# JBCproject.net
KiCad netlist of a schematic drawn in EAGLE
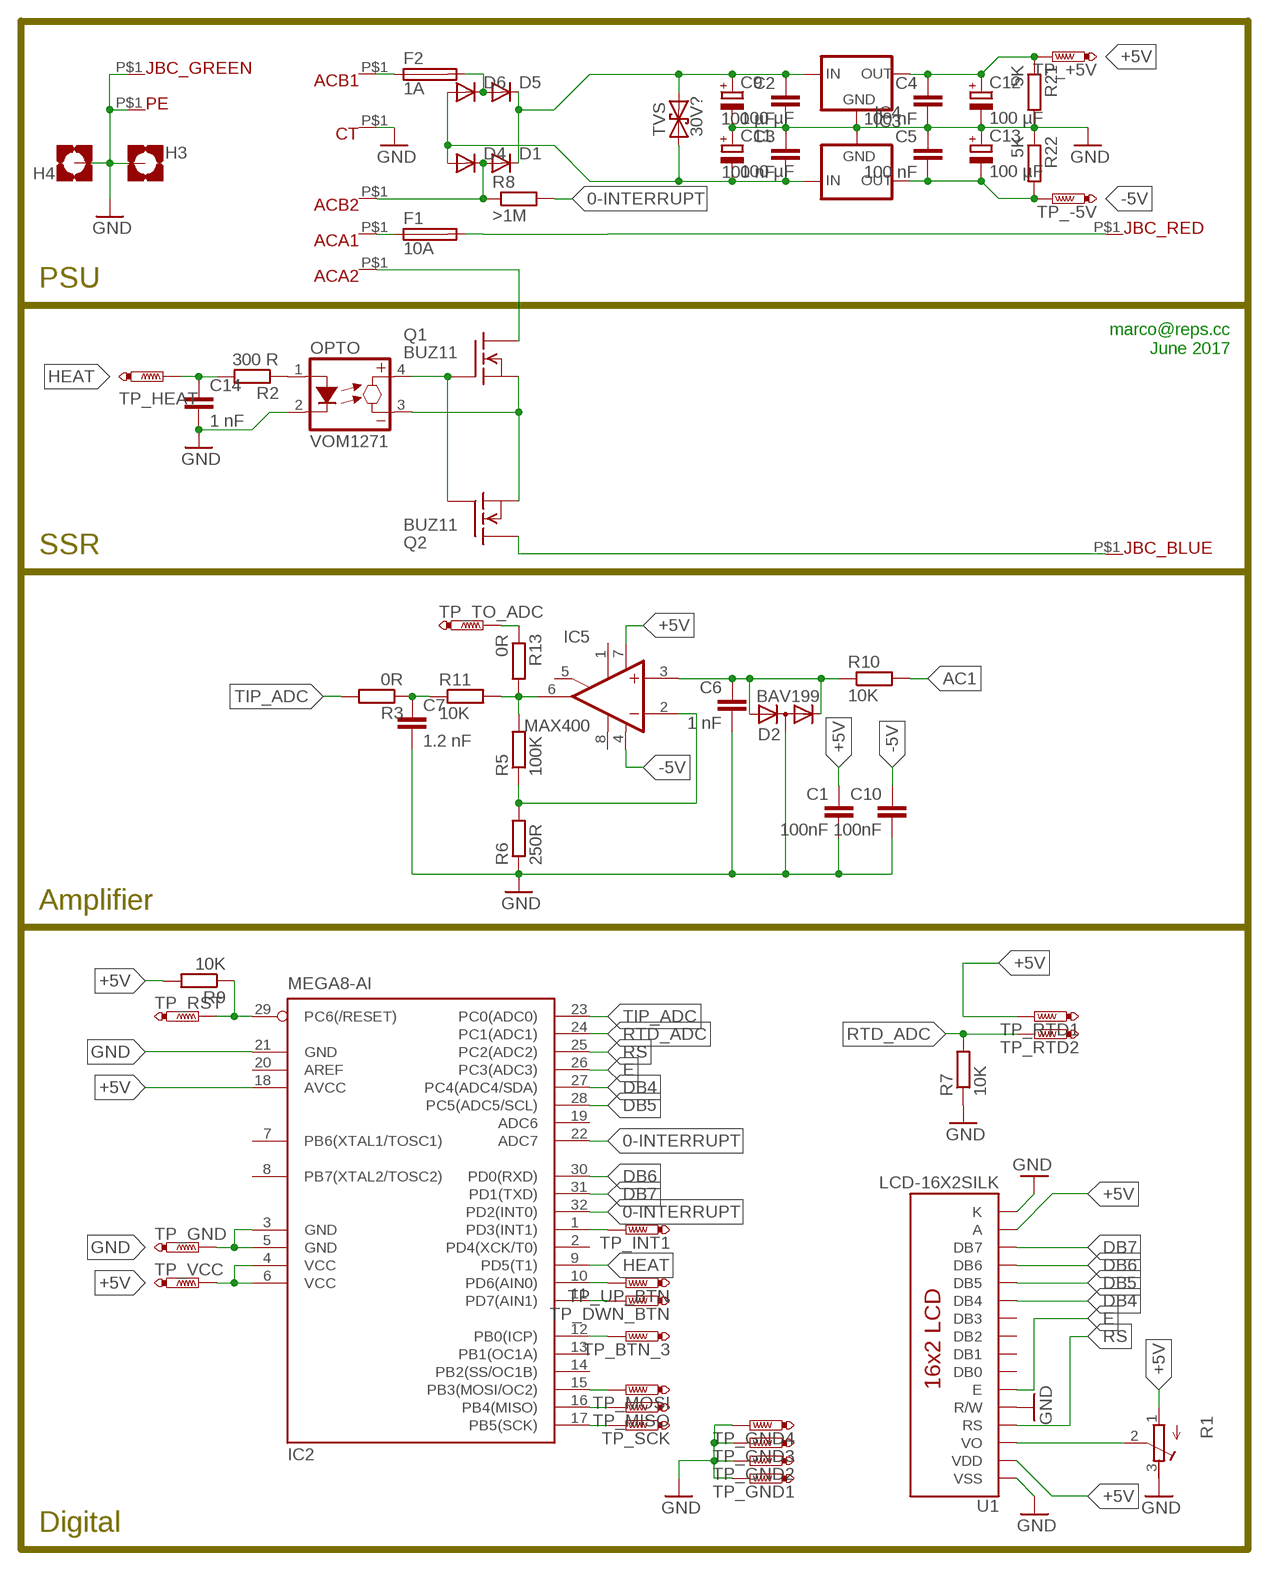
[diagram p0: schematic, sheet 1]

(export (version "E")
  (design (tool "Eeschema 10.0.6"))
  (components
    (comp (ref "ACA1")
      (value "1MMPIN")
      (footprint "eagle-import:1MMPIN")
      (libsource (lib "eagle-import") (part "1MMPIN"))
    )
    (comp (ref "ACA2")
      (value "1MMPIN")
      (footprint "eagle-import:1MMPIN")
      (libsource (lib "eagle-import") (part "1MMPIN"))
    )
    (comp (ref "ACB1")
      (value "1MMPIN")
      (footprint "eagle-import:1MMPIN")
      (libsource (lib "eagle-import") (part "1MMPIN"))
    )
    (comp (ref "ACB2")
      (value "1MMPIN")
      (footprint "eagle-import:1MMPIN")
      (libsource (lib "eagle-import") (part "1MMPIN"))
    )
    (comp (ref "C1")
      (value "100nF")
      (footprint "eagle-import:C1206")
      (libsource (lib "eagle-import") (part "C-EUC1206"))
    )
    (comp (ref "C2")
      (value "100 µF")
      (footprint "eagle-import:C1206")
      (libsource (lib "eagle-import") (part "C-EUC1206"))
    )
    (comp (ref "C3")
      (value "100 nF")
      (footprint "eagle-import:C1206")
      (libsource (lib "eagle-import") (part "C-EUC1206"))
    )
    (comp (ref "C4")
      (value "100 nF")
      (footprint "eagle-import:C1206")
      (libsource (lib "eagle-import") (part "C-EUC1206"))
    )
    (comp (ref "C5")
      (value "100 nF")
      (footprint "eagle-import:C1206")
      (libsource (lib "eagle-import") (part "C-EUC1206"))
    )
    (comp (ref "C6")
      (value "1 nF")
      (footprint "eagle-import:C1206")
      (libsource (lib "eagle-import") (part "C-EUC1206"))
    )
    (comp (ref "C7")
      (value "1.2 nF")
      (footprint "eagle-import:C1206")
      (libsource (lib "eagle-import") (part "C-EUC1206"))
    )
    (comp (ref "C9")
      (value "100 µF")
      (footprint "eagle-import:175TMP-0810")
      (libsource (lib "eagle-import") (part "CPOL-EU175TMP-0810"))
    )
    (comp (ref "C10")
      (value "100nF")
      (footprint "eagle-import:C1206")
      (libsource (lib "eagle-import") (part "C-EUC1206"))
    )
    (comp (ref "C11")
      (value "100 µF")
      (footprint "eagle-import:175TMP-0810")
      (libsource (lib "eagle-import") (part "CPOL-EU175TMP-0810"))
    )
    (comp (ref "C12")
      (value "100 µF")
      (footprint "eagle-import:175TMP-0810")
      (libsource (lib "eagle-import") (part "CPOL-EU175TMP-0810"))
    )
    (comp (ref "C13")
      (value "100 µF")
      (footprint "eagle-import:175TMP-0810")
      (libsource (lib "eagle-import") (part "CPOL-EU175TMP-0810"))
    )
    (comp (ref "C14")
      (value "1 nF")
      (footprint "eagle-import:C1206")
      (libsource (lib "eagle-import") (part "C-EUC1206"))
    )
    (comp (ref "CT")
      (value "1MMPIN")
      (footprint "eagle-import:1MMPIN")
      (libsource (lib "eagle-import") (part "1MMPIN"))
    )
    (comp (ref "D1")
      (value "ES2D")
      (footprint "eagle-import:SMB")
      (libsource (lib "eagle-import") (part "ES2D"))
    )
    (comp (ref "D2")
      (value "BAV199")
      (footprint "eagle-import:SOT23")
      (libsource (lib "eagle-import") (part "BAV199"))
    )
    (comp (ref "D4")
      (value "ES2D")
      (footprint "eagle-import:SMB")
      (libsource (lib "eagle-import") (part "ES2D"))
    )
    (comp (ref "D5")
      (value "ES2D")
      (footprint "eagle-import:SMB")
      (libsource (lib "eagle-import") (part "ES2D"))
    )
    (comp (ref "D6")
      (value "ES2D")
      (footprint "eagle-import:SMB")
      (libsource (lib "eagle-import") (part "ES2D"))
    )
    (comp (ref "F1")
      (value "10A")
      (footprint "eagle-import:PICOFUSE")
      (libsource (lib "eagle-import") (part "PICOFUSE"))
    )
    (comp (ref "F2")
      (value "1A")
      (footprint "eagle-import:PICOFUSE")
      (libsource (lib "eagle-import") (part "PICOFUSE"))
    )
    (comp (ref "H3")
      (value "MOUNT-PAD-SQUARE3.0")
      (footprint "eagle-import:3,0-PAD-SQUARE")
      (libsource (lib "eagle-import") (part "MOUNT-PAD-SQUARE3.0"))
    )
    (comp (ref "H4")
      (value "MOUNT-PAD-SQUARE3.0")
      (footprint "eagle-import:3,0-PAD-SQUARE")
      (libsource (lib "eagle-import") (part "MOUNT-PAD-SQUARE3.0"))
    )
    (comp (ref "IC2")
      (value "MEGA8-AI")
      (footprint "eagle-import:TQFP32-08")
      (fields (field (name "MPN") "ATMEGA8-16AU"))
      (libsource (lib "eagle-import") (part "MEGA8-AI"))
    )
    (comp (ref "IC3")
      (value "78XXS")
      (footprint "eagle-import:78XXS")
      (libsource (lib "eagle-import") (part "78XXS"))
    )
    (comp (ref "IC4")
      (value "79XXS")
      (footprint "eagle-import:79XXS")
      (libsource (lib "eagle-import") (part "79XXS"))
    )
    (comp (ref "IC5")
      (value "MAX400")
      (footprint "eagle-import:DIL08")
      (libsource (lib "eagle-import") (part "MAX400MJA"))
    )
    (comp (ref "JBC_BLUE")
      (value "1MMPIN")
      (footprint "eagle-import:1MMPIN")
      (libsource (lib "eagle-import") (part "1MMPIN"))
    )
    (comp (ref "JBC_GREEN")
      (value "1MMPIN")
      (footprint "eagle-import:1MMPIN")
      (libsource (lib "eagle-import") (part "1MMPIN"))
    )
    (comp (ref "JBC_RED")
      (value "1MMPIN")
      (footprint "eagle-import:1MMPIN")
      (libsource (lib "eagle-import") (part "1MMPIN"))
    )
    (comp (ref "OPTO")
      (value "VOM1271")
      (footprint "eagle-import:SOP-4")
      (libsource (lib "eagle-import") (part "VOM1271"))
    )
    (comp (ref "PE")
      (value "1MMPIN")
      (footprint "eagle-import:1MMPIN")
      (libsource (lib "eagle-import") (part "1MMPIN"))
    )
    (comp (ref "Q1")
      (value "BUZ11")
      (footprint "eagle-import:TO220")
      (libsource (lib "eagle-import") (part "BUZ11"))
    )
    (comp (ref "Q2")
      (value "BUZ11")
      (footprint "eagle-import:TO220")
      (libsource (lib "eagle-import") (part "BUZ11"))
    )
    (comp (ref "R1")
      (value "R-TRIMM4G/J")
      (footprint "eagle-import:RTRIM4G_J")
      (libsource (lib "eagle-import") (part "R-TRIMM4G/J"))
    )
    (comp (ref "R2")
      (value "300 R")
      (footprint "eagle-import:R1206")
      (libsource (lib "eagle-import") (part "R-EU_R1206"))
    )
    (comp (ref "R3")
      (value "0R")
      (footprint "eagle-import:R1206")
      (libsource (lib "eagle-import") (part "R-EU_R1206"))
    )
    (comp (ref "R5")
      (value "100K")
      (footprint "eagle-import:R1206")
      (libsource (lib "eagle-import") (part "R-EU_R1206"))
    )
    (comp (ref "R6")
      (value "250R")
      (footprint "eagle-import:R1206")
      (libsource (lib "eagle-import") (part "R-EU_R1206"))
    )
    (comp (ref "R7")
      (value "10K")
      (footprint "eagle-import:R1206")
      (libsource (lib "eagle-import") (part "R-EU_R1206"))
    )
    (comp (ref "R8")
      (value ">1M")
      (footprint "eagle-import:R1206")
      (libsource (lib "eagle-import") (part "R-EU_R1206"))
    )
    (comp (ref "R9")
      (value "10K")
      (footprint "eagle-import:R1206")
      (libsource (lib "eagle-import") (part "R-EU_R1206"))
    )
    (comp (ref "R10")
      (value "10K")
      (footprint "eagle-import:R1206")
      (libsource (lib "eagle-import") (part "R-EU_R1206"))
    )
    (comp (ref "R11")
      (value "10K")
      (footprint "eagle-import:R1206")
      (libsource (lib "eagle-import") (part "R-EU_R1206"))
    )
    (comp (ref "R13")
      (value "0R")
      (footprint "eagle-import:R1206")
      (libsource (lib "eagle-import") (part "R-EU_R1206"))
    )
    (comp (ref "R21")
      (value "5K")
      (footprint "eagle-import:R1206")
      (libsource (lib "eagle-import") (part "R-EU_R1206"))
    )
    (comp (ref "R22")
      (value "5K")
      (footprint "eagle-import:R1206")
      (libsource (lib "eagle-import") (part "R-EU_R1206"))
    )
    (comp (ref "TP_+5V")
      (value "PTR1TP20R")
      (footprint "eagle-import:TP20R")
      (libsource (lib "eagle-import") (part "PTR1TP20R"))
    )
    (comp (ref "TP_-5V")
      (value "PTR1TP20R")
      (footprint "eagle-import:TP20R")
      (libsource (lib "eagle-import") (part "PTR1TP20R"))
    )
    (comp (ref "TP_BTN_3")
      (value "PTR1TP20R")
      (footprint "eagle-import:TP20R")
      (libsource (lib "eagle-import") (part "PTR1TP20R"))
    )
    (comp (ref "TP_DWN_BTN")
      (value "PTR1TP20R")
      (footprint "eagle-import:TP20R")
      (libsource (lib "eagle-import") (part "PTR1TP20R"))
    )
    (comp (ref "TP_GND")
      (value "PTR1TP20R")
      (footprint "eagle-import:TP20R")
      (libsource (lib "eagle-import") (part "PTR1TP20R"))
    )
    (comp (ref "TP_GND1")
      (value "PTR1TP20R")
      (footprint "eagle-import:TP20R")
      (libsource (lib "eagle-import") (part "PTR1TP20R"))
    )
    (comp (ref "TP_GND2")
      (value "PTR1TP20R")
      (footprint "eagle-import:TP20R")
      (libsource (lib "eagle-import") (part "PTR1TP20R"))
    )
    (comp (ref "TP_GND3")
      (value "PTR1TP20R")
      (footprint "eagle-import:TP20R")
      (libsource (lib "eagle-import") (part "PTR1TP20R"))
    )
    (comp (ref "TP_GND4")
      (value "PTR1TP20R")
      (footprint "eagle-import:TP20R")
      (libsource (lib "eagle-import") (part "PTR1TP20R"))
    )
    (comp (ref "TP_HEAT")
      (value "PTR1TP20R")
      (footprint "eagle-import:TP20R")
      (libsource (lib "eagle-import") (part "PTR1TP20R"))
    )
    (comp (ref "TP_INT1")
      (value "PTR1TP20R")
      (footprint "eagle-import:TP20R")
      (libsource (lib "eagle-import") (part "PTR1TP20R"))
    )
    (comp (ref "TP_MISO")
      (value "PTR1TP20R")
      (footprint "eagle-import:TP20R")
      (libsource (lib "eagle-import") (part "PTR1TP20R"))
    )
    (comp (ref "TP_MOSI")
      (value "PTR1TP20R")
      (footprint "eagle-import:TP20R")
      (libsource (lib "eagle-import") (part "PTR1TP20R"))
    )
    (comp (ref "TP_RST")
      (value "PTR1TP20R")
      (footprint "eagle-import:TP20R")
      (libsource (lib "eagle-import") (part "PTR1TP20R"))
    )
    (comp (ref "TP_RTD1")
      (value "PTR1TP20R")
      (footprint "eagle-import:TP20R")
      (libsource (lib "eagle-import") (part "PTR1TP20R"))
    )
    (comp (ref "TP_RTD2")
      (value "PTR1TP20R")
      (footprint "eagle-import:TP20R")
      (libsource (lib "eagle-import") (part "PTR1TP20R"))
    )
    (comp (ref "TP_SCK")
      (value "PTR1TP20R")
      (footprint "eagle-import:TP20R")
      (libsource (lib "eagle-import") (part "PTR1TP20R"))
    )
    (comp (ref "TP_TO_ADC")
      (value "PTR1TP20R")
      (footprint "eagle-import:TP20R")
      (libsource (lib "eagle-import") (part "PTR1TP20R"))
    )
    (comp (ref "TP_UP_BTN")
      (value "PTR1TP20R")
      (footprint "eagle-import:TP20R")
      (libsource (lib "eagle-import") (part "PTR1TP20R"))
    )
    (comp (ref "TP_VCC")
      (value "PTR1TP20R")
      (footprint "eagle-import:TP20R")
      (libsource (lib "eagle-import") (part "PTR1TP20R"))
    )
    (comp (ref "TVS")
      (value "30V?")
      (footprint "eagle-import:SMA-DIODE")
      (libsource (lib "eagle-import") (part "TVS"))
    )
    (comp (ref "U1")
      (value "LCD-16X2SILK")
      (footprint "eagle-import:LCD-16X2")
      (libsource (lib "eagle-import") (part "LCD-16X2SILK"))
    )
  )
  (nets
    (net (code "1") (name "+5V") (class "Default")
      (node (ref "C1") (pin "1") (pinfunction "1_1") (pintype "passive"))
      (node (ref "C12") (pin "+") (pinfunction "+_+") (pintype "passive"))
      (node (ref "C4") (pin "1") (pinfunction "1_1") (pintype "passive"))
      (node (ref "IC2") (pin "18") (pinfunction "AVCC_18") (pintype "power_in"))
      (node (ref "IC2") (pin "4") (pinfunction "VCC_4") (pintype "power_in"))
      (node (ref "IC2") (pin "6") (pinfunction "VCC_6") (pintype "power_in"))
      (node (ref "IC3") (pin "OUT") (pinfunction "OUT_OUT") (pintype "passive"))
      (node (ref "IC5") (pin "7") (pinfunction "V+_7") (pintype "power_in"))
      (node (ref "R1") (pin "1") (pinfunction "A_1") (pintype "passive"))
      (node (ref "R21") (pin "1") (pinfunction "1_1") (pintype "passive"))
      (node (ref "R9") (pin "2") (pinfunction "2_2") (pintype "passive"))
      (node (ref "TP_+5V") (pin "TP") (pinfunction "TP_TP") (pintype "input"))
      (node (ref "TP_RTD1") (pin "TP") (pinfunction "TP_TP") (pintype "input"))
      (node (ref "TP_VCC") (pin "TP") (pinfunction "TP_TP") (pintype "input"))
      (node (ref "U1") (pin "15") (pinfunction "A_15") (pintype "power_in"))
      (node (ref "U1") (pin "2") (pinfunction "VDD_2") (pintype "power_in"))
    )
    (net (code "2") (name "-5V") (class "Default")
      (node (ref "C10") (pin "1") (pinfunction "1_1") (pintype "passive"))
      (node (ref "C13") (pin "-") (pinfunction "-_-") (pintype "passive"))
      (node (ref "C5") (pin "2") (pinfunction "2_2") (pintype "passive"))
      (node (ref "IC4") (pin "OUT") (pinfunction "OUT_OUT") (pintype "passive"))
      (node (ref "IC5") (pin "4") (pinfunction "V-_4") (pintype "power_in"))
      (node (ref "R22") (pin "2") (pinfunction "2_2") (pintype "passive"))
      (node (ref "TP_-5V") (pin "TP") (pinfunction "TP_TP") (pintype "input"))
    )
    (net (code "3") (name "/OPAMPOUT") (class "Default")
      (node (ref "IC5") (pin "6") (pinfunction "OUT_6") (pintype "output"))
      (node (ref "R11") (pin "2") (pinfunction "2_2") (pintype "passive"))
      (node (ref "R13") (pin "1") (pinfunction "1_1") (pintype "passive"))
      (node (ref "R13") (pin "2") (pinfunction "2_2") (pintype "passive"))
      (node (ref "R5") (pin "2") (pinfunction "2_2") (pintype "passive"))
      (node (ref "TP_TO_ADC") (pin "TP") (pinfunction "TP_TP") (pintype "input"))
    )
    (net (code "4") (name "0-INTERRUPT") (class "Default")
      (node (ref "IC2") (pin "22") (pinfunction "ADC7_22") (pintype "bidirectional"))
      (node (ref "IC2") (pin "32") (pinfunction "PD2(INT0)_32") (pintype "bidirectional"))
      (node (ref "R8") (pin "2") (pinfunction "2_2") (pintype "passive"))
    )
    (net (code "5") (name "AC1") (class "Default")
      (node (ref "F1") (pin "2") (pinfunction "2_2") (pintype "passive"))
      (node (ref "JBC_RED") (pin "P$1") (pinfunction "P$1_P$1") (pintype "bidirectional"))
      (node (ref "R10") (pin "2") (pinfunction "2_2") (pintype "passive"))
    )
    (net (code "6") (name "DB4") (class "Default")
      (node (ref "IC2") (pin "27") (pinfunction "PC4(ADC4/SDA)_27") (pintype "bidirectional"))
      (node (ref "U1") (pin "11") (pinfunction "DB4_11") (pintype "bidirectional"))
    )
    (net (code "7") (name "DB5") (class "Default")
      (node (ref "IC2") (pin "28") (pinfunction "PC5(ADC5/SCL)_28") (pintype "bidirectional"))
      (node (ref "U1") (pin "12") (pinfunction "DB5_12") (pintype "bidirectional"))
    )
    (net (code "8") (name "DB6") (class "Default")
      (node (ref "IC2") (pin "30") (pinfunction "PD0(RXD)_30") (pintype "bidirectional"))
      (node (ref "U1") (pin "13") (pinfunction "DB6_13") (pintype "bidirectional"))
    )
    (net (code "9") (name "DB7") (class "Default")
      (node (ref "IC2") (pin "31") (pinfunction "PD1(TXD)_31") (pintype "bidirectional"))
      (node (ref "U1") (pin "14") (pinfunction "DB7_14") (pintype "bidirectional"))
    )
    (net (code "10") (name "E") (class "Default")
      (node (ref "IC2") (pin "26") (pinfunction "PC3(ADC3)_26") (pintype "bidirectional"))
      (node (ref "U1") (pin "6") (pinfunction "E_6") (pintype "input"))
    )
    (net (code "11") (name "GND") (class "Default")
      (node (ref "C1") (pin "2") (pinfunction "2_2") (pintype "passive"))
      (node (ref "C10") (pin "2") (pinfunction "2_2") (pintype "passive"))
      (node (ref "C11") (pin "+") (pinfunction "+_+") (pintype "passive"))
      (node (ref "C12") (pin "-") (pinfunction "-_-") (pintype "passive"))
      (node (ref "C13") (pin "+") (pinfunction "+_+") (pintype "passive"))
      (node (ref "C14") (pin "2") (pinfunction "2_2") (pintype "passive"))
      (node (ref "C2") (pin "2") (pinfunction "2_2") (pintype "passive"))
      (node (ref "C3") (pin "1") (pinfunction "1_1") (pintype "passive"))
      (node (ref "C4") (pin "2") (pinfunction "2_2") (pintype "passive"))
      (node (ref "C5") (pin "1") (pinfunction "1_1") (pintype "passive"))
      (node (ref "C6") (pin "2") (pinfunction "2_2") (pintype "passive"))
      (node (ref "C7") (pin "2") (pinfunction "2_2") (pintype "passive"))
      (node (ref "C9") (pin "-") (pinfunction "-_-") (pintype "passive"))
      (node (ref "CT") (pin "P$1") (pinfunction "P$1_P$1") (pintype "bidirectional"))
      (node (ref "D2") (pin "3") (pinfunction "AC_3") (pintype "passive"))
      (node (ref "H3") (pin "B3,0") (pinfunction "MOUNT_B3,0") (pintype "passive"))
      (node (ref "H4") (pin "B3,0") (pinfunction "MOUNT_B3,0") (pintype "passive"))
      (node (ref "IC2") (pin "21") (pinfunction "GND_21") (pintype "power_in"))
      (node (ref "IC2") (pin "3") (pinfunction "GND_3") (pintype "power_in"))
      (node (ref "IC2") (pin "5") (pinfunction "GND_5") (pintype "power_in"))
      (node (ref "IC3") (pin "GND") (pinfunction "GND_GND") (pintype "input"))
      (node (ref "IC4") (pin "GND") (pinfunction "GND_GND") (pintype "input"))
      (node (ref "JBC_GREEN") (pin "P$1") (pinfunction "P$1_P$1") (pintype "bidirectional"))
      (node (ref "OPTO") (pin "2") (pinfunction "2_2") (pintype "passive"))
      (node (ref "PE") (pin "P$1") (pinfunction "P$1_P$1") (pintype "bidirectional"))
      (node (ref "R1") (pin "3") (pinfunction "E_3") (pintype "passive"))
      (node (ref "R21") (pin "2") (pinfunction "2_2") (pintype "passive"))
      (node (ref "R22") (pin "1") (pinfunction "1_1") (pintype "passive"))
      (node (ref "R6") (pin "1") (pinfunction "1_1") (pintype "passive"))
      (node (ref "R7") (pin "1") (pinfunction "1_1") (pintype "passive"))
      (node (ref "TP_GND") (pin "TP") (pinfunction "TP_TP") (pintype "input"))
      (node (ref "TP_GND1") (pin "TP") (pinfunction "TP_TP") (pintype "input"))
      (node (ref "TP_GND2") (pin "TP") (pinfunction "TP_TP") (pintype "input"))
      (node (ref "TP_GND3") (pin "TP") (pinfunction "TP_TP") (pintype "input"))
      (node (ref "TP_GND4") (pin "TP") (pinfunction "TP_TP") (pintype "input"))
      (node (ref "U1") (pin "1") (pinfunction "VSS_1") (pintype "power_in"))
      (node (ref "U1") (pin "16") (pinfunction "K_16") (pintype "power_in"))
      (node (ref "U1") (pin "5") (pinfunction "R/W_5") (pintype "input"))
    )
    (net (code "12") (name "HEAT") (class "Default")
      (node (ref "C14") (pin "1") (pinfunction "1_1") (pintype "passive"))
      (node (ref "IC2") (pin "9") (pinfunction "PD5(T1)_9") (pintype "bidirectional"))
      (node (ref "R2") (pin "2") (pinfunction "2_2") (pintype "passive"))
      (node (ref "TP_HEAT") (pin "TP") (pinfunction "TP_TP") (pintype "input"))
    )
    (net (code "13") (name "Net-(ACA1-PadP$1)") (class "Default")
      (node (ref "ACA1") (pin "P$1") (pinfunction "P$1_P$1") (pintype "bidirectional"))
      (node (ref "F1") (pin "1") (pinfunction "1_1") (pintype "passive"))
    )
    (net (code "14") (name "Net-(ACB1-PadP$1)") (class "Default")
      (node (ref "ACB1") (pin "P$1") (pinfunction "P$1_P$1") (pintype "bidirectional"))
      (node (ref "F2") (pin "1") (pinfunction "1_1") (pintype "passive"))
    )
    (net (code "15") (name "Net-(ACB2-PadP$1)") (class "Default")
      (node (ref "ACB2") (pin "P$1") (pinfunction "P$1_P$1") (pintype "bidirectional"))
      (node (ref "D1") (pin "A") (pinfunction "A_A") (pintype "passive"))
      (node (ref "D4") (pin "C") (pinfunction "C_C") (pintype "passive"))
      (node (ref "R8") (pin "1") (pinfunction "1_1") (pintype "passive"))
    )
    (net (code "16") (name "Net-(C7-Pad1)") (class "Default")
      (node (ref "C7") (pin "1") (pinfunction "1_1") (pintype "passive"))
      (node (ref "R11") (pin "1") (pinfunction "1_1") (pintype "passive"))
      (node (ref "R3") (pin "1") (pinfunction "1_1") (pintype "passive"))
    )
    (net (code "17") (name "Net-(D2-A)") (class "Default")
      (node (ref "C6") (pin "1") (pinfunction "1_1") (pintype "passive"))
      (node (ref "D2") (pin "1") (pinfunction "A_1") (pintype "passive"))
      (node (ref "D2") (pin "2") (pinfunction "C_2") (pintype "passive"))
      (node (ref "IC5") (pin "3") (pinfunction "+IN_3") (pintype "input"))
      (node (ref "R10") (pin "1") (pinfunction "1_1") (pintype "passive"))
    )
    (net (code "18") (name "Net-(D5-PadA)") (class "Default")
      (node (ref "D5") (pin "A") (pinfunction "A_A") (pintype "passive"))
      (node (ref "D6") (pin "C") (pinfunction "C_C") (pintype "passive"))
      (node (ref "F2") (pin "2") (pinfunction "2_2") (pintype "passive"))
    )
    (net (code "19") (name "Net-(IC2-PB0(ICP))") (class "Default")
      (node (ref "IC2") (pin "12") (pinfunction "PB0(ICP)_12") (pintype "bidirectional"))
      (node (ref "TP_BTN_3") (pin "TP") (pinfunction "TP_TP") (pintype "input"))
    )
    (net (code "20") (name "Net-(IC2-PB3(MOSI{slash}OC2))") (class "Default")
      (node (ref "IC2") (pin "15") (pinfunction "PB3(MOSI/OC2)_15") (pintype "bidirectional"))
      (node (ref "TP_MOSI") (pin "TP") (pinfunction "TP_TP") (pintype "input"))
    )
    (net (code "21") (name "Net-(IC2-PB4(MISO))") (class "Default")
      (node (ref "IC2") (pin "16") (pinfunction "PB4(MISO)_16") (pintype "bidirectional"))
      (node (ref "TP_MISO") (pin "TP") (pinfunction "TP_TP") (pintype "input"))
    )
    (net (code "22") (name "Net-(IC2-PB5(SCK))") (class "Default")
      (node (ref "IC2") (pin "17") (pinfunction "PB5(SCK)_17") (pintype "bidirectional"))
      (node (ref "TP_SCK") (pin "TP") (pinfunction "TP_TP") (pintype "input"))
    )
    (net (code "23") (name "Net-(IC2-PC6({slash}RESET))") (class "Default")
      (node (ref "IC2") (pin "29") (pinfunction "PC6(/RESET)_29") (pintype "bidirectional"))
      (node (ref "R9") (pin "1") (pinfunction "1_1") (pintype "passive"))
      (node (ref "TP_RST") (pin "TP") (pinfunction "TP_TP") (pintype "input"))
    )
    (net (code "24") (name "Net-(IC2-PD3(INT1))") (class "Default")
      (node (ref "IC2") (pin "1") (pinfunction "PD3(INT1)_1") (pintype "bidirectional"))
      (node (ref "TP_INT1") (pin "TP") (pinfunction "TP_TP") (pintype "input"))
    )
    (net (code "25") (name "Net-(IC2-PD6(AIN0))") (class "Default")
      (node (ref "IC2") (pin "10") (pinfunction "PD6(AIN0)_10") (pintype "bidirectional"))
      (node (ref "TP_UP_BTN") (pin "TP") (pinfunction "TP_TP") (pintype "input"))
    )
    (net (code "26") (name "Net-(IC2-PD7(AIN1))") (class "Default")
      (node (ref "IC2") (pin "11") (pinfunction "PD7(AIN1)_11") (pintype "bidirectional"))
      (node (ref "TP_DWN_BTN") (pin "TP") (pinfunction "TP_TP") (pintype "input"))
    )
    (net (code "27") (name "Net-(IC5--IN)") (class "Default")
      (node (ref "IC5") (pin "2") (pinfunction "-IN_2") (pintype "input"))
      (node (ref "R5") (pin "1") (pinfunction "1_1") (pintype "passive"))
      (node (ref "R6") (pin "2") (pinfunction "2_2") (pintype "passive"))
    )
    (net (code "28") (name "Net-(OPTO-Pad1)") (class "Default")
      (node (ref "OPTO") (pin "1") (pinfunction "1_1") (pintype "passive"))
      (node (ref "R2") (pin "1") (pinfunction "1_1") (pintype "passive"))
    )
    (net (code "29") (name "Net-(Q1-D)") (class "Default")
      (node (ref "ACA2") (pin "P$1") (pinfunction "P$1_P$1") (pintype "bidirectional"))
      (node (ref "Q1") (pin "2") (pinfunction "D_2") (pintype "passive"))
    )
    (net (code "30") (name "Net-(Q1-G)") (class "Default")
      (node (ref "OPTO") (pin "4") (pinfunction "4_4") (pintype "passive"))
      (node (ref "Q1") (pin "1") (pinfunction "G_1") (pintype "passive"))
      (node (ref "Q2") (pin "1") (pinfunction "G_1") (pintype "passive"))
    )
    (net (code "31") (name "Net-(Q1-S)") (class "Default")
      (node (ref "OPTO") (pin "3") (pinfunction "3_3") (pintype "passive"))
      (node (ref "Q1") (pin "3") (pinfunction "S_3") (pintype "passive"))
      (node (ref "Q2") (pin "3") (pinfunction "S_3") (pintype "passive"))
    )
    (net (code "32") (name "Net-(Q2-D)") (class "Default")
      (node (ref "JBC_BLUE") (pin "P$1") (pinfunction "P$1_P$1") (pintype "bidirectional"))
      (node (ref "Q2") (pin "2") (pinfunction "D_2") (pintype "passive"))
    )
    (net (code "33") (name "Net-(R1-S)") (class "Default")
      (node (ref "R1") (pin "2") (pinfunction "S_2") (pintype "passive"))
      (node (ref "U1") (pin "3") (pinfunction "VO_3") (pintype "bidirectional"))
    )
    (net (code "34") (name "Net-(TVS-1)") (class "Default")
      (node (ref "C11") (pin "-") (pinfunction "-_-") (pintype "passive"))
      (node (ref "C3") (pin "2") (pinfunction "2_2") (pintype "passive"))
      (node (ref "D4") (pin "A") (pinfunction "A_A") (pintype "passive"))
      (node (ref "D6") (pin "A") (pinfunction "A_A") (pintype "passive"))
      (node (ref "IC4") (pin "IN") (pinfunction "IN_IN") (pintype "input"))
      (node (ref "TVS") (pin "A") (pinfunction "1_A") (pintype "passive"))
    )
    (net (code "35") (name "Net-(TVS-2)") (class "Default")
      (node (ref "C2") (pin "1") (pinfunction "1_1") (pintype "passive"))
      (node (ref "C9") (pin "+") (pinfunction "+_+") (pintype "passive"))
      (node (ref "D1") (pin "C") (pinfunction "C_C") (pintype "passive"))
      (node (ref "D5") (pin "C") (pinfunction "C_C") (pintype "passive"))
      (node (ref "IC3") (pin "IN") (pinfunction "IN_IN") (pintype "input"))
      (node (ref "TVS") (pin "C") (pinfunction "2_C") (pintype "passive"))
    )
    (net (code "36") (name "RS") (class "Default")
      (node (ref "IC2") (pin "25") (pinfunction "PC2(ADC2)_25") (pintype "bidirectional"))
      (node (ref "U1") (pin "4") (pinfunction "RS_4") (pintype "input"))
    )
    (net (code "37") (name "RTD_ADC") (class "Default")
      (node (ref "IC2") (pin "24") (pinfunction "PC1(ADC1)_24") (pintype "bidirectional"))
      (node (ref "R7") (pin "2") (pinfunction "2_2") (pintype "passive"))
      (node (ref "TP_RTD2") (pin "TP") (pinfunction "TP_TP") (pintype "input"))
    )
    (net (code "38") (name "TIP_ADC") (class "Default")
      (node (ref "IC2") (pin "23") (pinfunction "PC0(ADC0)_23") (pintype "bidirectional"))
      (node (ref "R3") (pin "2") (pinfunction "2_2") (pintype "passive"))
    )
    (net (code "39") (name "unconnected-(IC2-ADC6-Pad19)") (class "Default")
      (node (ref "IC2") (pin "19") (pinfunction "ADC6_19") (pintype "bidirectional"))
    )
    (net (code "40") (name "unconnected-(IC2-AREF-Pad20)") (class "Default")
      (node (ref "IC2") (pin "20") (pinfunction "AREF_20") (pintype "passive"))
    )
    (net (code "41") (name "unconnected-(IC2-PB1(OC1A)-Pad13)") (class "Default")
      (node (ref "IC2") (pin "13") (pinfunction "PB1(OC1A)_13") (pintype "bidirectional"))
    )
    (net (code "42") (name "unconnected-(IC2-PB2(SS{slash}OC1B)-Pad14)") (class "Default")
      (node (ref "IC2") (pin "14") (pinfunction "PB2(SS/OC1B)_14") (pintype "bidirectional"))
    )
    (net (code "43") (name "unconnected-(IC2-PB6(XTAL1{slash}TOSC1)-Pad7)") (class "Default")
      (node (ref "IC2") (pin "7") (pinfunction "PB6(XTAL1/TOSC1)_7") (pintype "bidirectional"))
    )
    (net (code "44") (name "unconnected-(IC2-PB7(XTAL2{slash}TOSC2)-Pad8)") (class "Default")
      (node (ref "IC2") (pin "8") (pinfunction "PB7(XTAL2/TOSC2)_8") (pintype "bidirectional"))
    )
    (net (code "45") (name "unconnected-(IC2-PD4(XCK{slash}T0)-Pad2)") (class "Default")
      (node (ref "IC2") (pin "2") (pinfunction "PD4(XCK/T0)_2") (pintype "bidirectional"))
    )
    (net (code "46") (name "unconnected-(IC5-NC-Pad5)") (class "Default")
      (node (ref "IC5") (pin "5") (pinfunction "NC_5") (pintype "no_connect"))
    )
    (net (code "47") (name "unconnected-(IC5-VOS-Pad1)") (class "Default")
      (node (ref "IC5") (pin "1") (pinfunction "VOS_1") (pintype "passive"))
    )
    (net (code "48") (name "unconnected-(IC5-VOS-Pad8)") (class "Default")
      (node (ref "IC5") (pin "8") (pinfunction "VOS_8") (pintype "passive"))
    )
    (net (code "49") (name "unconnected-(U1-DB0-Pad7)") (class "Default")
      (node (ref "U1") (pin "7") (pinfunction "DB0_7") (pintype "bidirectional"))
    )
    (net (code "50") (name "unconnected-(U1-DB1-Pad8)") (class "Default")
      (node (ref "U1") (pin "8") (pinfunction "DB1_8") (pintype "bidirectional"))
    )
    (net (code "51") (name "unconnected-(U1-DB2-Pad9)") (class "Default")
      (node (ref "U1") (pin "9") (pinfunction "DB2_9") (pintype "bidirectional"))
    )
    (net (code "52") (name "unconnected-(U1-DB3-Pad10)") (class "Default")
      (node (ref "U1") (pin "10") (pinfunction "DB3_10") (pintype "bidirectional"))
    )
  )
)
